# RadioMusic_F_rev2-2.net
KiCad netlist of a schematic drawn in EAGLE
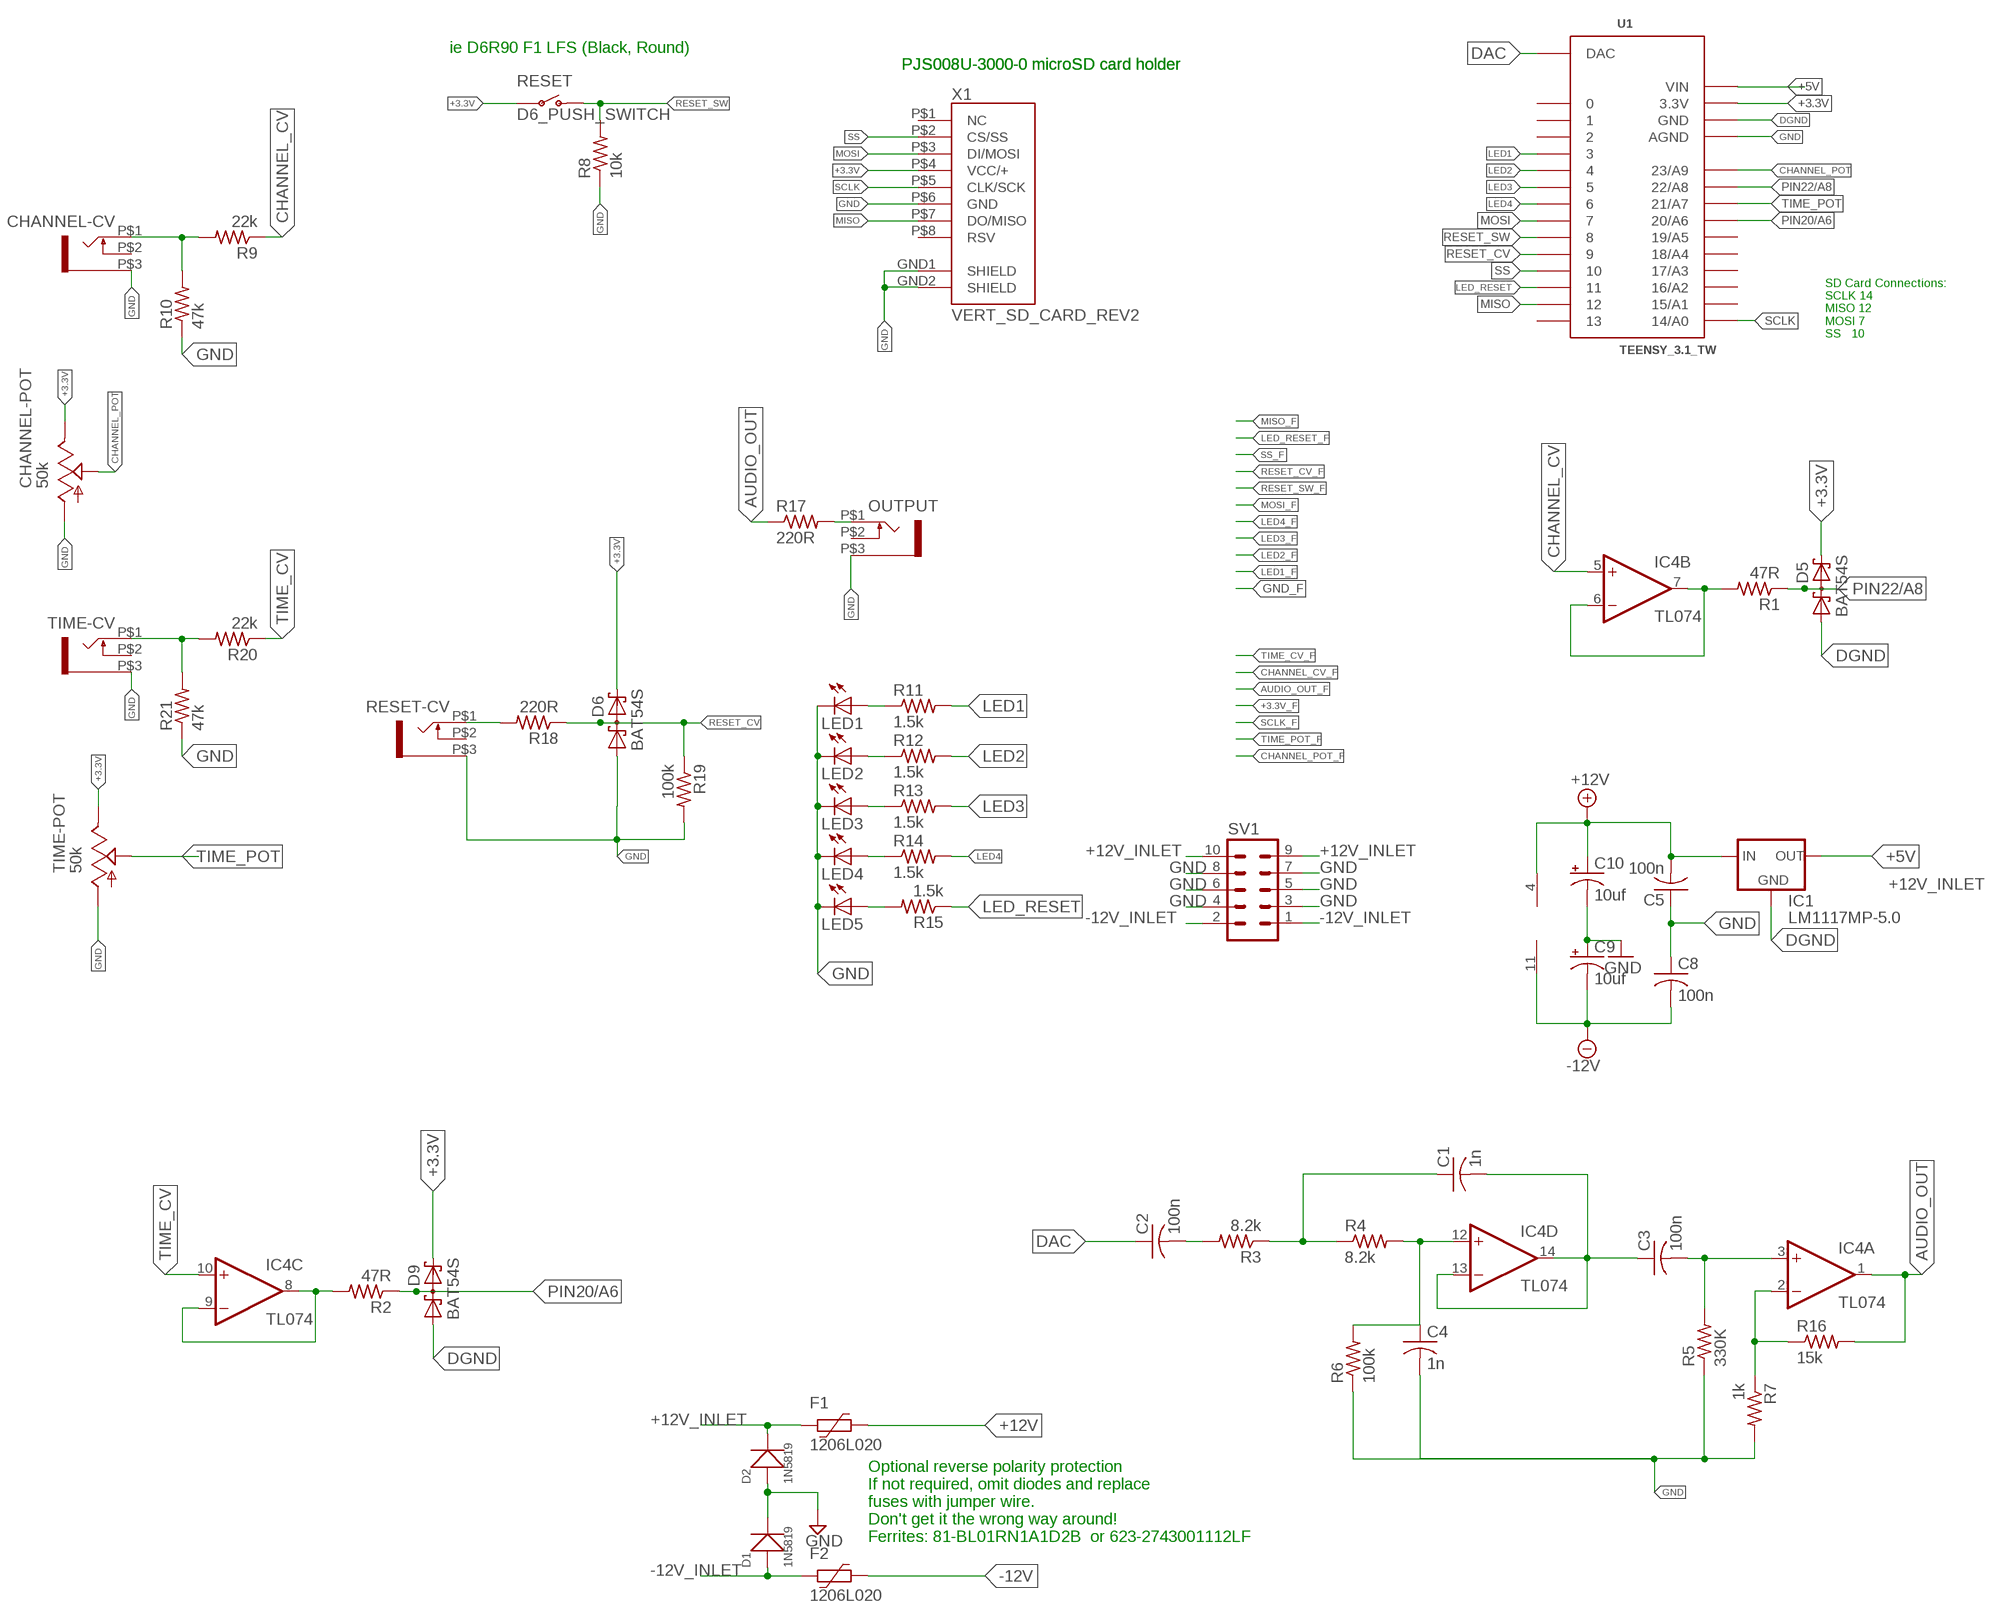
[diagram p0: schematic, sheet 1]

(export (version "E")
  (design (tool "Eeschema 10.0.6"))
  (components
    (comp (ref "C1")
      (value "1n")
      (footprint "eagle-import:C0805")
      (libsource (lib "eagle-import") (part "C-USC0805"))
    )
    (comp (ref "C2")
      (value "100n")
      (footprint "eagle-import:C0805")
      (libsource (lib "eagle-import") (part "C-USC0805"))
    )
    (comp (ref "C3")
      (value "100n")
      (footprint "eagle-import:C0805")
      (libsource (lib "eagle-import") (part "C-USC0805"))
    )
    (comp (ref "C4")
      (value "1n")
      (footprint "eagle-import:C0805")
      (libsource (lib "eagle-import") (part "C-USC0805"))
    )
    (comp (ref "C5")
      (value "100n")
      (footprint "eagle-import:C0805")
      (libsource (lib "eagle-import") (part "C-USC0805"))
    )
    (comp (ref "C8")
      (value "100n")
      (footprint "eagle-import:C0805")
      (libsource (lib "eagle-import") (part "C-USC0805"))
    )
    (comp (ref "C9")
      (value "10uf")
      (footprint "eagle-import:PANASONIC_B")
      (libsource (lib "eagle-import") (part "CPOL-USB"))
    )
    (comp (ref "C10")
      (value "10uf")
      (footprint "eagle-import:PANASONIC_B")
      (libsource (lib "eagle-import") (part "CPOL-USB"))
    )
    (comp (ref "CHANNEL-CV")
      (value "WQP-PJ301M-12_JACK")
      (footprint "eagle-import:WQP-PJ301M-12_JACK")
      (libsource (lib "eagle-import") (part "WQP-PJ301M-12_JACK"))
    )
    (comp (ref "CHANNEL-POT")
      (value "50k")
      (footprint "eagle-import:EVUF")
      (libsource (lib "eagle-import") (part "ALPHA-9MMAF2"))
    )
    (comp (ref "D1")
      (value "1N5819")
      (footprint "eagle-import:SOD-123")
      (fields (field (name "MPN") "B0540W"))
      (libsource (lib "eagle-import") (part "SMD-DIODE-SCHOTTKY-40V-500MA(SOD-123)"))
    )
    (comp (ref "D2")
      (value "1N5819")
      (footprint "eagle-import:SOD-123")
      (fields (field (name "MPN") "B0540W"))
      (libsource (lib "eagle-import") (part "SMD-DIODE-SCHOTTKY-40V-500MA(SOD-123)"))
    )
    (comp (ref "D5")
      (value "BAT54S")
      (footprint "eagle-import:SOT23")
      (libsource (lib "eagle-import") (part "BAT54S"))
    )
    (comp (ref "D6")
      (value "BAT54S")
      (footprint "eagle-import:SOT23")
      (libsource (lib "eagle-import") (part "BAT54S"))
    )
    (comp (ref "D9")
      (value "BAT54S")
      (footprint "eagle-import:SOT23")
      (libsource (lib "eagle-import") (part "BAT54S"))
    )
    (comp (ref "F1")
      (value "1206L020")
      (footprint "eagle-import:1206L")
      (fields (field (name "MF") "Littelfuse"))
      (libsource (lib "eagle-import") (part "?1206L020"))
    )
    (comp (ref "F2")
      (value "1206L020")
      (footprint "eagle-import:1206L")
      (fields (field (name "MF") "Littelfuse"))
      (libsource (lib "eagle-import") (part "?1206L020"))
    )
    (comp (ref "IC1")
      (value "LM1117MP-5.0")
      (footprint "eagle-import:SOT223")
      (fields (field (name "MF") "Texas Instruments"))
      (libsource (lib "eagle-import") (part "LM1117?-MP5.0"))
    )
    (comp (ref "IC4")
      (value "TL074")
      (footprint "eagle-import:SO14")
      (libsource (lib "eagle-import") (part "TL074D"))
    )
    (comp (ref "LED1")
      (value "LED3MM")
      (footprint "eagle-import:LED3MM")
      (libsource (lib "eagle-import") (part "LED3MM"))
    )
    (comp (ref "LED2")
      (value "LED3MM")
      (footprint "eagle-import:LED3MM")
      (libsource (lib "eagle-import") (part "LED3MM"))
    )
    (comp (ref "LED3")
      (value "LED3MM")
      (footprint "eagle-import:LED3MM")
      (libsource (lib "eagle-import") (part "LED3MM"))
    )
    (comp (ref "LED4")
      (value "LED3MM")
      (footprint "eagle-import:LED3MM")
      (libsource (lib "eagle-import") (part "LED3MM"))
    )
    (comp (ref "LED5")
      (value "LED3MM")
      (footprint "eagle-import:LED3MM")
      (libsource (lib "eagle-import") (part "LED3MM"))
    )
    (comp (ref "OUTPUT")
      (value "WQP-PJ301M-12_JACK")
      (footprint "eagle-import:WQP-PJ301M-12_JACK")
      (libsource (lib "eagle-import") (part "WQP-PJ301M-12_JACK"))
    )
    (comp (ref "R1")
      (value "47R")
      (footprint "eagle-import:R0805")
      (libsource (lib "eagle-import") (part "R-US_R0805"))
    )
    (comp (ref "R2")
      (value "47R")
      (footprint "eagle-import:R0805")
      (libsource (lib "eagle-import") (part "R-US_R0805"))
    )
    (comp (ref "R3")
      (value "8.2k")
      (footprint "eagle-import:R0805")
      (libsource (lib "eagle-import") (part "R-US_R0805"))
    )
    (comp (ref "R4")
      (value "8.2k")
      (footprint "eagle-import:R0805")
      (libsource (lib "eagle-import") (part "R-US_R0805"))
    )
    (comp (ref "R5")
      (value "330K")
      (footprint "eagle-import:R0805")
      (libsource (lib "eagle-import") (part "R-US_R0805"))
    )
    (comp (ref "R6")
      (value "100k")
      (footprint "eagle-import:R0805")
      (libsource (lib "eagle-import") (part "R-US_R0805"))
    )
    (comp (ref "R7")
      (value "1k")
      (footprint "eagle-import:R0805")
      (libsource (lib "eagle-import") (part "R-US_R0805"))
    )
    (comp (ref "R8")
      (value "10k")
      (footprint "eagle-import:R0805")
      (libsource (lib "eagle-import") (part "R-US_R0805"))
    )
    (comp (ref "R9")
      (value "22k")
      (footprint "eagle-import:R0805")
      (libsource (lib "eagle-import") (part "R-US_R0805"))
    )
    (comp (ref "R10")
      (value "47k")
      (footprint "eagle-import:R0805")
      (libsource (lib "eagle-import") (part "R-US_R0805"))
    )
    (comp (ref "R11")
      (value "1.5k")
      (footprint "eagle-import:R0805")
      (libsource (lib "eagle-import") (part "R-US_R0805"))
    )
    (comp (ref "R12")
      (value "1.5k")
      (footprint "eagle-import:R0805")
      (libsource (lib "eagle-import") (part "R-US_R0805"))
    )
    (comp (ref "R13")
      (value "1.5k")
      (footprint "eagle-import:R0805")
      (libsource (lib "eagle-import") (part "R-US_R0805"))
    )
    (comp (ref "R14")
      (value "1.5k")
      (footprint "eagle-import:R0805")
      (libsource (lib "eagle-import") (part "R-US_R0805"))
    )
    (comp (ref "R15")
      (value "1.5k")
      (footprint "eagle-import:R0805")
      (libsource (lib "eagle-import") (part "R-US_R0805"))
    )
    (comp (ref "R16")
      (value "15k")
      (footprint "eagle-import:R0805")
      (libsource (lib "eagle-import") (part "R-US_R0805"))
    )
    (comp (ref "R17")
      (value "220R")
      (footprint "eagle-import:R0805")
      (libsource (lib "eagle-import") (part "R-US_R0805"))
    )
    (comp (ref "R18")
      (value "220R")
      (footprint "eagle-import:R0805")
      (libsource (lib "eagle-import") (part "R-US_R0805"))
    )
    (comp (ref "R19")
      (value "100k")
      (footprint "eagle-import:R0805")
      (libsource (lib "eagle-import") (part "R-US_R0805"))
    )
    (comp (ref "R20")
      (value "22k")
      (footprint "eagle-import:R0805")
      (libsource (lib "eagle-import") (part "R-US_R0805"))
    )
    (comp (ref "R21")
      (value "47k")
      (footprint "eagle-import:R0805")
      (libsource (lib "eagle-import") (part "R-US_R0805"))
    )
    (comp (ref "RESET")
      (value "D6_PUSH_SWITCH")
      (footprint "eagle-import:D6_BUTTON_RND")
      (libsource (lib "eagle-import") (part "D6_PUSH_SWITCH"))
    )
    (comp (ref "RESET-CV")
      (value "WQP-PJ301M-12_JACK")
      (footprint "eagle-import:WQP-PJ301M-12_JACK")
      (libsource (lib "eagle-import") (part "WQP-PJ301M-12_JACK"))
    )
    (comp (ref "SV1")
      (value "10_PIN_HEADER")
      (footprint "eagle-import:MA05-2")
      (libsource (lib "eagle-import") (part "10_PIN_HEADER"))
    )
    (comp (ref "TIME-CV")
      (value "WQP-PJ301M-12_JACK")
      (footprint "eagle-import:WQP-PJ301M-12_JACK")
      (libsource (lib "eagle-import") (part "WQP-PJ301M-12_JACK"))
    )
    (comp (ref "TIME-POT")
      (value "50k")
      (footprint "eagle-import:EVUF")
      (libsource (lib "eagle-import") (part "ALPHA-9MMAF2"))
    )
    (comp (ref "U1")
      (value "TEENSY_3.1_TW")
      (footprint "eagle-import:TEENSY_3.1_TW")
      (libsource (lib "eagle-import") (part "TEENSY_3.1_TW"))
    )
    (comp (ref "X1")
      (value "VERT_SD_CARD_REV2")
      (footprint "eagle-import:VERT_MICROSD_REV2")
      (libsource (lib "eagle-import") (part "VERT_SD_CARD_REV2"))
    )
  )
  (nets
    (net (code "1") (name "+3.3V") (class "Default")
      (node (ref "CHANNEL-POT") (pin "3") (pinfunction "E_3") (pintype "passive"))
      (node (ref "D5") (pin "2") (pinfunction "C2_2") (pintype "passive"))
      (node (ref "D6") (pin "2") (pinfunction "C2_2") (pintype "passive"))
      (node (ref "D9") (pin "2") (pinfunction "C2_2") (pintype "passive"))
      (node (ref "RESET") (pin "P$3") (pinfunction "P_P$3") (pintype "passive"))
      (node (ref "RESET") (pin "P$4") (pinfunction "P_P$4") (pintype "passive"))
      (node (ref "TIME-POT") (pin "3") (pinfunction "E_3") (pintype "passive"))
      (node (ref "U1") (pin "3.3V") (pinfunction "3.3V_3.3V") (pintype "power_in"))
      (node (ref "X1") (pin "P$4") (pinfunction "VCC/+_P$4") (pintype "bidirectional"))
    )
    (net (code "3") (name "+5V") (class "Default")
      (node (ref "IC1") (pin "2") (pinfunction "OUT_2") (pintype "passive"))
      (node (ref "IC1") (pin "4") (pinfunction "OUT_4") (pintype "passive"))
      (node (ref "U1") (pin "VIN") (pinfunction "VIN_VIN") (pintype "power_in"))
    )
    (net (code "4") (name "+12V") (class "Default")
      (node (ref "C10") (pin "+") (pinfunction "+_+") (pintype "passive"))
      (node (ref "C5") (pin "2") (pinfunction "2_2") (pintype "passive"))
      (node (ref "F1") (pin "1") (pinfunction "1_1") (pintype "passive"))
      (node (ref "IC1") (pin "3") (pinfunction "IN_3") (pintype "input"))
      (node (ref "IC4") (pin "4") (pinfunction "V+_4") (pintype "power_in"))
    )
    (net (code "5") (name "-12V") (class "Default")
      (node (ref "C8") (pin "2") (pinfunction "2_2") (pintype "passive"))
      (node (ref "C9") (pin "-") (pinfunction "-_-") (pintype "passive"))
      (node (ref "F2") (pin "1") (pinfunction "1_1") (pintype "passive"))
      (node (ref "IC4") (pin "11") (pinfunction "V-_11") (pintype "power_in"))
    )
    (net (code "6") (name "/+12V_INLET") (class "Default")
      (node (ref "D2") (pin "-") (pinfunction "-_-") (pintype "passive"))
      (node (ref "F1") (pin "2") (pinfunction "2_2") (pintype "passive"))
      (node (ref "SV1") (pin "10") (pinfunction "10_10") (pintype "passive"))
      (node (ref "SV1") (pin "9") (pinfunction "9_9") (pintype "passive"))
    )
    (net (code "7") (name "/-12V_INLET") (class "Default")
      (node (ref "D1") (pin "+") (pinfunction "+_+") (pintype "passive"))
      (node (ref "F2") (pin "2") (pinfunction "2_2") (pintype "passive"))
      (node (ref "SV1") (pin "1") (pinfunction "1_1") (pintype "passive"))
      (node (ref "SV1") (pin "2") (pinfunction "2_2") (pintype "passive"))
    )
    (net (code "8") (name "AUDIO_OUT") (class "Default")
      (node (ref "IC4") (pin "1") (pinfunction "OUT_1") (pintype "output"))
      (node (ref "R16") (pin "2") (pinfunction "2_2") (pintype "passive"))
      (node (ref "R17") (pin "1") (pinfunction "1_1") (pintype "passive"))
    )
    (net (code "10") (name "CHANNEL_CV") (class "Default")
      (node (ref "IC4") (pin "5") (pinfunction "+IN_5") (pintype "input"))
      (node (ref "R9") (pin "1") (pinfunction "1_1") (pintype "passive"))
    )
    (net (code "12") (name "CHANNEL_POT") (class "Default")
      (node (ref "CHANNEL-POT") (pin "2") (pinfunction "S_2") (pintype "passive"))
      (node (ref "U1") (pin "23/A9") (pinfunction "23/A9_23/A9") (pintype "bidirectional"))
    )
    (net (code "14") (name "DAC") (class "Default")
      (node (ref "C2") (pin "1") (pinfunction "1_1") (pintype "passive"))
      (node (ref "U1") (pin "DAC") (pinfunction "DAC_DAC") (pintype "bidirectional"))
    )
    (net (code "15") (name "DGND") (class "Default")
      (node (ref "D5") (pin "1") (pinfunction "A1_1") (pintype "passive"))
      (node (ref "D9") (pin "1") (pinfunction "A1_1") (pintype "passive"))
      (node (ref "IC1") (pin "1") (pinfunction "GND_1") (pintype "input"))
      (node (ref "U1") (pin "GND") (pinfunction "GND_GND") (pintype "power_in"))
    )
    (net (code "16") (name "GND") (class "Default")
      (node (ref "C10") (pin "-") (pinfunction "-_-") (pintype "passive"))
      (node (ref "C4") (pin "2") (pinfunction "2_2") (pintype "passive"))
      (node (ref "C5") (pin "1") (pinfunction "1_1") (pintype "passive"))
      (node (ref "C8") (pin "1") (pinfunction "1_1") (pintype "passive"))
      (node (ref "C9") (pin "+") (pinfunction "+_+") (pintype "passive"))
      (node (ref "CHANNEL-CV") (pin "P$3") (pinfunction "1_P$3") (pintype "passive"))
      (node (ref "CHANNEL-POT") (pin "1") (pinfunction "A_1") (pintype "passive"))
      (node (ref "D1") (pin "-") (pinfunction "-_-") (pintype "passive"))
      (node (ref "D2") (pin "+") (pinfunction "+_+") (pintype "passive"))
      (node (ref "D6") (pin "1") (pinfunction "A1_1") (pintype "passive"))
      (node (ref "LED1") (pin "K") (pinfunction "C_K") (pintype "passive"))
      (node (ref "LED2") (pin "K") (pinfunction "C_K") (pintype "passive"))
      (node (ref "LED3") (pin "K") (pinfunction "C_K") (pintype "passive"))
      (node (ref "LED4") (pin "K") (pinfunction "C_K") (pintype "passive"))
      (node (ref "LED5") (pin "K") (pinfunction "C_K") (pintype "passive"))
      (node (ref "OUTPUT") (pin "P$3") (pinfunction "1_P$3") (pintype "passive"))
      (node (ref "R10") (pin "1") (pinfunction "1_1") (pintype "passive"))
      (node (ref "R19") (pin "2") (pinfunction "2_2") (pintype "passive"))
      (node (ref "R21") (pin "1") (pinfunction "1_1") (pintype "passive"))
      (node (ref "R5") (pin "1") (pinfunction "1_1") (pintype "passive"))
      (node (ref "R6") (pin "1") (pinfunction "1_1") (pintype "passive"))
      (node (ref "R7") (pin "2") (pinfunction "2_2") (pintype "passive"))
      (node (ref "R8") (pin "1") (pinfunction "1_1") (pintype "passive"))
      (node (ref "RESET-CV") (pin "P$3") (pinfunction "1_P$3") (pintype "passive"))
      (node (ref "SV1") (pin "3") (pinfunction "3_3") (pintype "passive"))
      (node (ref "SV1") (pin "4") (pinfunction "4_4") (pintype "passive"))
      (node (ref "SV1") (pin "5") (pinfunction "5_5") (pintype "passive"))
      (node (ref "SV1") (pin "6") (pinfunction "6_6") (pintype "passive"))
      (node (ref "SV1") (pin "7") (pinfunction "7_7") (pintype "passive"))
      (node (ref "SV1") (pin "8") (pinfunction "8_8") (pintype "passive"))
      (node (ref "TIME-CV") (pin "P$3") (pinfunction "1_P$3") (pintype "passive"))
      (node (ref "TIME-POT") (pin "1") (pinfunction "A_1") (pintype "passive"))
      (node (ref "U1") (pin "AGND") (pinfunction "AGND_AGND") (pintype "power_in"))
      (node (ref "X1") (pin "GND1") (pinfunction "SHIELD_GND1") (pintype "bidirectional"))
      (node (ref "X1") (pin "GND2") (pinfunction "SHIELD_GND2") (pintype "bidirectional"))
      (node (ref "X1") (pin "P$6") (pinfunction "GND_P$6") (pintype "bidirectional"))
    )
    (net (code "18") (name "LED1") (class "Default")
      (node (ref "R11") (pin "2") (pinfunction "2_2") (pintype "passive"))
      (node (ref "U1") (pin "3") (pinfunction "3_3") (pintype "bidirectional"))
    )
    (net (code "20") (name "LED2") (class "Default")
      (node (ref "R12") (pin "2") (pinfunction "2_2") (pintype "passive"))
      (node (ref "U1") (pin "4") (pinfunction "4_4") (pintype "bidirectional"))
    )
    (net (code "22") (name "LED3") (class "Default")
      (node (ref "R13") (pin "2") (pinfunction "2_2") (pintype "passive"))
      (node (ref "U1") (pin "5") (pinfunction "5_5") (pintype "bidirectional"))
    )
    (net (code "24") (name "LED4") (class "Default")
      (node (ref "R14") (pin "2") (pinfunction "2_2") (pintype "passive"))
      (node (ref "U1") (pin "6") (pinfunction "6_6") (pintype "bidirectional"))
    )
    (net (code "26") (name "LED_RESET") (class "Default")
      (node (ref "R15") (pin "1") (pinfunction "1_1") (pintype "passive"))
      (node (ref "U1") (pin "11") (pinfunction "11_11") (pintype "bidirectional"))
    )
    (net (code "28") (name "MISO") (class "Default")
      (node (ref "U1") (pin "12") (pinfunction "12_12") (pintype "bidirectional"))
      (node (ref "X1") (pin "P$7") (pinfunction "DO/MISO_P$7") (pintype "bidirectional"))
    )
    (net (code "30") (name "MOSI") (class "Default")
      (node (ref "U1") (pin "7") (pinfunction "7_7") (pintype "bidirectional"))
      (node (ref "X1") (pin "P$3") (pinfunction "DI/MOSI_P$3") (pintype "bidirectional"))
    )
    (net (code "32") (name "Net-(C1-Pad1)") (class "Default")
      (node (ref "C1") (pin "1") (pinfunction "1_1") (pintype "passive"))
      (node (ref "R3") (pin "1") (pinfunction "1_1") (pintype "passive"))
      (node (ref "R4") (pin "1") (pinfunction "1_1") (pintype "passive"))
    )
    (net (code "33") (name "Net-(C2-Pad2)") (class "Default")
      (node (ref "C2") (pin "2") (pinfunction "2_2") (pintype "passive"))
      (node (ref "R3") (pin "2") (pinfunction "2_2") (pintype "passive"))
    )
    (net (code "34") (name "Net-(CHANNEL-CV-2)") (class "Default")
      (node (ref "CHANNEL-CV") (pin "P$1") (pinfunction "2_P$1") (pintype "passive"))
      (node (ref "R10") (pin "2") (pinfunction "2_2") (pintype "passive"))
      (node (ref "R9") (pin "2") (pinfunction "2_2") (pintype "passive"))
    )
    (net (code "35") (name "Net-(IC4A-+IN)") (class "Default")
      (node (ref "C3") (pin "2") (pinfunction "2_2") (pintype "passive"))
      (node (ref "IC4") (pin "3") (pinfunction "+IN_3") (pintype "input"))
      (node (ref "R5") (pin "2") (pinfunction "2_2") (pintype "passive"))
    )
    (net (code "36") (name "Net-(IC4A--IN)") (class "Default")
      (node (ref "IC4") (pin "2") (pinfunction "-IN_2") (pintype "input"))
      (node (ref "R16") (pin "1") (pinfunction "1_1") (pintype "passive"))
      (node (ref "R7") (pin "1") (pinfunction "1_1") (pintype "passive"))
    )
    (net (code "37") (name "Net-(IC4B--IN)") (class "Default")
      (node (ref "IC4") (pin "6") (pinfunction "-IN_6") (pintype "input"))
      (node (ref "IC4") (pin "7") (pinfunction "OUT_7") (pintype "output"))
      (node (ref "R1") (pin "2") (pinfunction "2_2") (pintype "passive"))
    )
    (net (code "38") (name "Net-(IC4C--IN)") (class "Default")
      (node (ref "IC4") (pin "8") (pinfunction "OUT_8") (pintype "output"))
      (node (ref "IC4") (pin "9") (pinfunction "-IN_9") (pintype "input"))
      (node (ref "R2") (pin "2") (pinfunction "2_2") (pintype "passive"))
    )
    (net (code "39") (name "Net-(IC4D-+IN)") (class "Default")
      (node (ref "C4") (pin "1") (pinfunction "1_1") (pintype "passive"))
      (node (ref "IC4") (pin "12") (pinfunction "+IN_12") (pintype "input"))
      (node (ref "R4") (pin "2") (pinfunction "2_2") (pintype "passive"))
      (node (ref "R6") (pin "2") (pinfunction "2_2") (pintype "passive"))
    )
    (net (code "40") (name "Net-(IC4D--IN)") (class "Default")
      (node (ref "C1") (pin "2") (pinfunction "2_2") (pintype "passive"))
      (node (ref "C3") (pin "1") (pinfunction "1_1") (pintype "passive"))
      (node (ref "IC4") (pin "13") (pinfunction "-IN_13") (pintype "input"))
      (node (ref "IC4") (pin "14") (pinfunction "OUT_14") (pintype "output"))
    )
    (net (code "41") (name "Net-(LED1-PadA)") (class "Default")
      (node (ref "LED1") (pin "A") (pinfunction "A_A") (pintype "passive"))
      (node (ref "R11") (pin "1") (pinfunction "1_1") (pintype "passive"))
    )
    (net (code "42") (name "Net-(LED2-PadA)") (class "Default")
      (node (ref "LED2") (pin "A") (pinfunction "A_A") (pintype "passive"))
      (node (ref "R12") (pin "1") (pinfunction "1_1") (pintype "passive"))
    )
    (net (code "43") (name "Net-(LED3-PadA)") (class "Default")
      (node (ref "LED3") (pin "A") (pinfunction "A_A") (pintype "passive"))
      (node (ref "R13") (pin "1") (pinfunction "1_1") (pintype "passive"))
    )
    (net (code "44") (name "Net-(LED4-PadA)") (class "Default")
      (node (ref "LED4") (pin "A") (pinfunction "A_A") (pintype "passive"))
      (node (ref "R14") (pin "1") (pinfunction "1_1") (pintype "passive"))
    )
    (net (code "45") (name "Net-(LED5-PadA)") (class "Default")
      (node (ref "LED5") (pin "A") (pinfunction "A_A") (pintype "passive"))
      (node (ref "R15") (pin "2") (pinfunction "2_2") (pintype "passive"))
    )
    (net (code "46") (name "Net-(OUTPUT-2)") (class "Default")
      (node (ref "OUTPUT") (pin "P$1") (pinfunction "2_P$1") (pintype "passive"))
      (node (ref "R17") (pin "2") (pinfunction "2_2") (pintype "passive"))
    )
    (net (code "47") (name "Net-(RESET-CV-2)") (class "Default")
      (node (ref "R18") (pin "2") (pinfunction "2_2") (pintype "passive"))
      (node (ref "RESET-CV") (pin "P$1") (pinfunction "2_P$1") (pintype "passive"))
    )
    (net (code "48") (name "Net-(TIME-CV-2)") (class "Default")
      (node (ref "R20") (pin "2") (pinfunction "2_2") (pintype "passive"))
      (node (ref "R21") (pin "2") (pinfunction "2_2") (pintype "passive"))
      (node (ref "TIME-CV") (pin "P$1") (pinfunction "2_P$1") (pintype "passive"))
    )
    (net (code "49") (name "PIN20{slash}A6") (class "Default")
      (node (ref "D9") (pin "3") (pinfunction "C1A2_3") (pintype "passive"))
      (node (ref "R2") (pin "1") (pinfunction "1_1") (pintype "passive"))
      (node (ref "U1") (pin "20/A6") (pinfunction "20/A6_20/A6") (pintype "bidirectional"))
    )
    (net (code "50") (name "PIN22{slash}A8") (class "Default")
      (node (ref "D5") (pin "3") (pinfunction "C1A2_3") (pintype "passive"))
      (node (ref "R1") (pin "1") (pinfunction "1_1") (pintype "passive"))
      (node (ref "U1") (pin "22/A8") (pinfunction "22/A8_22/A8") (pintype "bidirectional"))
    )
    (net (code "51") (name "RESET_CV") (class "Default")
      (node (ref "D6") (pin "3") (pinfunction "C1A2_3") (pintype "passive"))
      (node (ref "R18") (pin "1") (pinfunction "1_1") (pintype "passive"))
      (node (ref "R19") (pin "1") (pinfunction "1_1") (pintype "passive"))
      (node (ref "U1") (pin "9") (pinfunction "9_9") (pintype "bidirectional"))
    )
    (net (code "53") (name "RESET_SW") (class "Default")
      (node (ref "R8") (pin "2") (pinfunction "2_2") (pintype "passive"))
      (node (ref "RESET") (pin "P$1") (pinfunction "O_P$1") (pintype "passive"))
      (node (ref "RESET") (pin "P$2") (pinfunction "O_P$2") (pintype "passive"))
      (node (ref "U1") (pin "8") (pinfunction "8_8") (pintype "bidirectional"))
    )
    (net (code "55") (name "SCLK") (class "Default")
      (node (ref "U1") (pin "14/A0") (pinfunction "14/A0_14/A0") (pintype "bidirectional"))
      (node (ref "X1") (pin "P$5") (pinfunction "CLK/SCK_P$5") (pintype "bidirectional"))
    )
    (net (code "57") (name "SS") (class "Default")
      (node (ref "U1") (pin "10") (pinfunction "10_10") (pintype "bidirectional"))
      (node (ref "X1") (pin "P$2") (pinfunction "CS/SS_P$2") (pintype "bidirectional"))
    )
    (net (code "59") (name "TIME_CV") (class "Default")
      (node (ref "IC4") (pin "10") (pinfunction "+IN_10") (pintype "input"))
      (node (ref "R20") (pin "1") (pinfunction "1_1") (pintype "passive"))
    )
    (net (code "61") (name "TIME_POT") (class "Default")
      (node (ref "TIME-POT") (pin "2") (pinfunction "S_2") (pintype "passive"))
      (node (ref "U1") (pin "21/A7") (pinfunction "21/A7_21/A7") (pintype "bidirectional"))
    )
    (net (code "63") (name "unconnected-(CHANNEL-CV-3-PadP$2)") (class "Default")
      (node (ref "CHANNEL-CV") (pin "P$2") (pinfunction "3_P$2") (pintype "passive"))
    )
    (net (code "64") (name "unconnected-(OUTPUT-3-PadP$2)") (class "Default")
      (node (ref "OUTPUT") (pin "P$2") (pinfunction "3_P$2") (pintype "passive"))
    )
    (net (code "65") (name "unconnected-(RESET-CV-3-PadP$2)") (class "Default")
      (node (ref "RESET-CV") (pin "P$2") (pinfunction "3_P$2") (pintype "passive"))
    )
    (net (code "66") (name "unconnected-(TIME-CV-3-PadP$2)") (class "Default")
      (node (ref "TIME-CV") (pin "P$2") (pinfunction "3_P$2") (pintype "passive"))
    )
    (net (code "67") (name "unconnected-(U1-Pad0)") (class "Default")
      (node (ref "U1") (pin "0") (pinfunction "0_0") (pintype "bidirectional"))
    )
    (net (code "68") (name "unconnected-(U1-Pad1)") (class "Default")
      (node (ref "U1") (pin "1") (pinfunction "1_1") (pintype "bidirectional"))
    )
    (net (code "69") (name "unconnected-(U1-Pad2)") (class "Default")
      (node (ref "U1") (pin "2") (pinfunction "2_2") (pintype "bidirectional"))
    )
    (net (code "70") (name "unconnected-(U1-Pad13)") (class "Default")
      (node (ref "U1") (pin "13") (pinfunction "13_13") (pintype "bidirectional"))
    )
    (net (code "71") (name "unconnected-(U1-Pad15{slash}A1)") (class "Default")
      (node (ref "U1") (pin "15/A1") (pinfunction "15/A1_15/A1") (pintype "bidirectional"))
    )
    (net (code "72") (name "unconnected-(U1-Pad16{slash}A2)") (class "Default")
      (node (ref "U1") (pin "16/A2") (pinfunction "16/A2_16/A2") (pintype "bidirectional"))
    )
    (net (code "73") (name "unconnected-(U1-Pad17{slash}A3)") (class "Default")
      (node (ref "U1") (pin "17/A3") (pinfunction "17/A3_17/A3") (pintype "bidirectional"))
    )
    (net (code "74") (name "unconnected-(U1-Pad18{slash}A4)") (class "Default")
      (node (ref "U1") (pin "18/A4") (pinfunction "18/A4_18/A4") (pintype "bidirectional"))
    )
    (net (code "75") (name "unconnected-(U1-Pad19{slash}A5)") (class "Default")
      (node (ref "U1") (pin "19/A5") (pinfunction "19/A5_19/A5") (pintype "bidirectional"))
    )
    (net (code "76") (name "unconnected-(X1-NC-PadP$1)") (class "Default")
      (node (ref "X1") (pin "P$1") (pinfunction "NC_P$1") (pintype "bidirectional"))
    )
    (net (code "77") (name "unconnected-(X1-RSV-PadP$8)") (class "Default")
      (node (ref "X1") (pin "P$8") (pinfunction "RSV_P$8") (pintype "bidirectional"))
    )
  )
)
